# Sheet1.net
KiCad netlist of a schematic drawn in Altium Designer
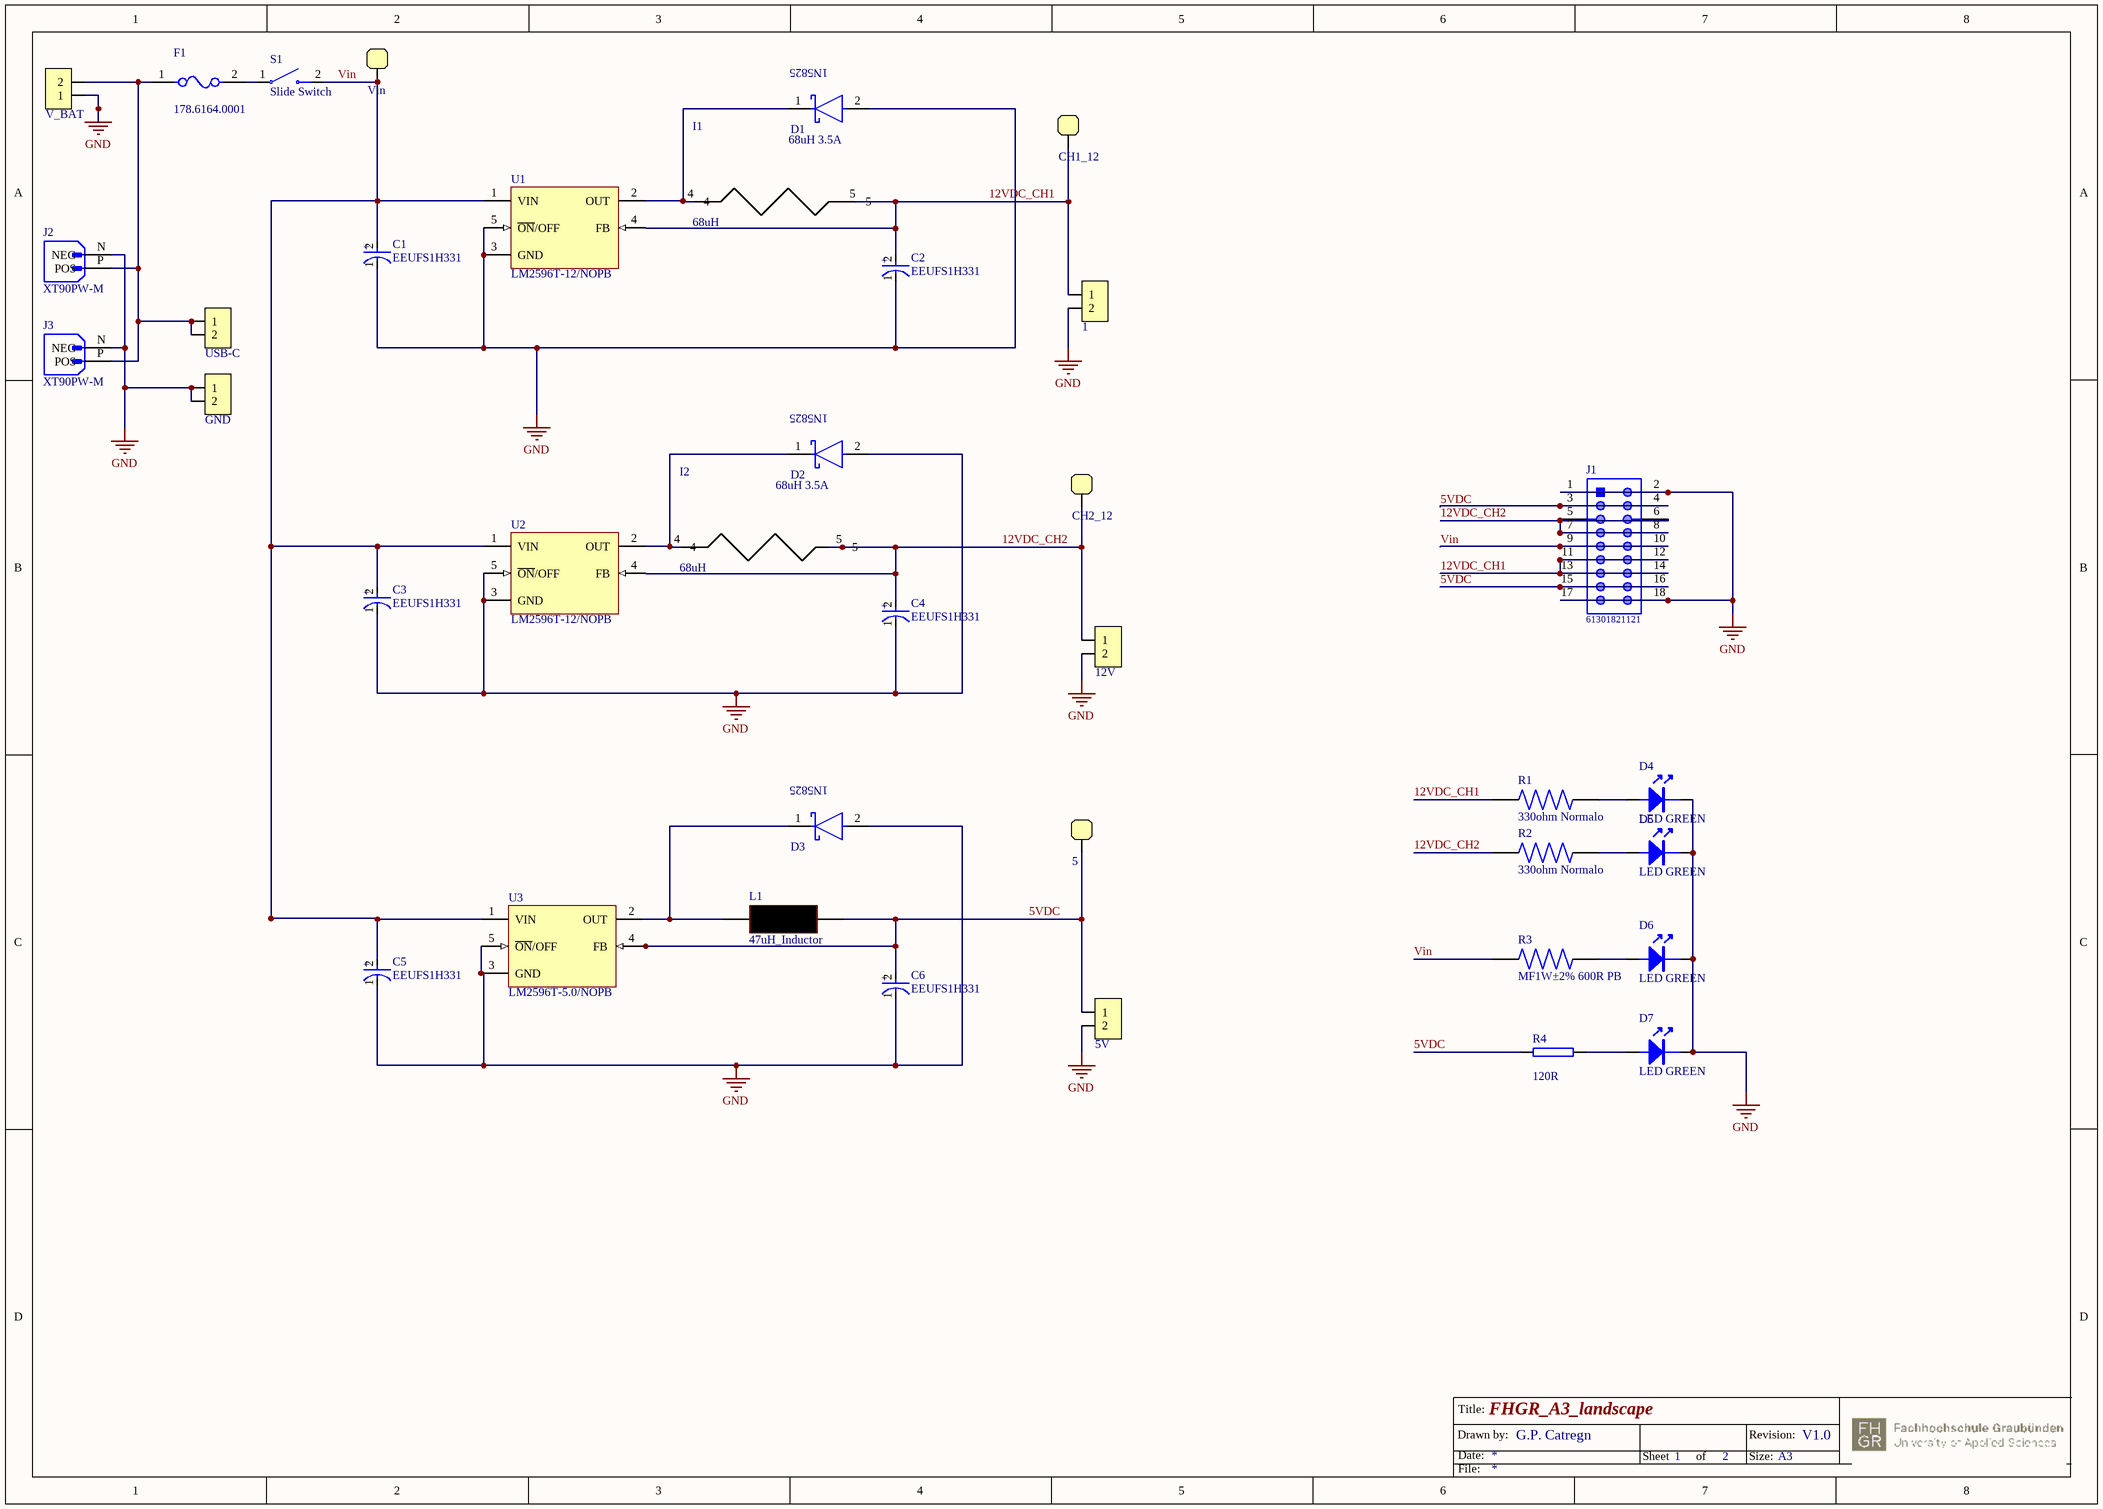
[diagram p0: Sheet1.SchDoc]

(export (version "E")
  (design (tool "Eeschema 10.0.6"))
  (components
    (comp (ref "1")
      (value "2Pin_Female")
      (footprint "OSTTE020104")
      (libsource (lib "FHGR_Altium_database") (part "Connector2Pin"))
    )
    (comp (ref "5") (value "MP") (footprint "MP_20") (libsource (lib "FHGR_Altium_database") (part "MP")))
    (comp (ref "5V")
      (value "2Pin_Female")
      (footprint "OSTTE020104")
      (libsource (lib "FHGR_Altium_database") (part "Connector2Pin"))
    )
    (comp (ref "12V")
      (value "2Pin_Female")
      (footprint "OSTTE020104")
      (libsource (lib "FHGR_Altium_database") (part "Connector2Pin"))
    )
    (comp (ref "C1")
      (value "EEUFS1H331")
      (footprint "FP-RAD-TH-D_10_0_5-L_20_2-MFG")
      (description "Aluminum Electrolytic Capacitors (Radial Lead Type) 330uF ±20% 50V")
      (libsource (lib "Altium Content Vault") (part "203bc49f2ac43e59fd269a8c329ed05"))
    )
    (comp (ref "C2")
      (value "EEUFS1H331")
      (footprint "FP-RAD-TH-D_10_0_5-L_20_2-MFG")
      (description "Aluminum Electrolytic Capacitors (Radial Lead Type) 330uF ±20% 50V")
      (libsource (lib "Altium Content Vault") (part "203bc49f2ac43e59fd269a8c329ed05"))
    )
    (comp (ref "C3")
      (value "EEUFS1H331")
      (footprint "FP-RAD-TH-D_10_0_5-L_20_2-MFG")
      (description "Aluminum Electrolytic Capacitors (Radial Lead Type) 330uF ±20% 50V")
      (libsource (lib "Altium Content Vault") (part "203bc49f2ac43e59fd269a8c329ed05"))
    )
    (comp (ref "C4")
      (value "EEUFS1H331")
      (footprint "FP-RAD-TH-D_10_0_5-L_20_2-MFG")
      (description "Aluminum Electrolytic Capacitors (Radial Lead Type) 330uF ±20% 50V")
      (libsource (lib "Altium Content Vault") (part "203bc49f2ac43e59fd269a8c329ed05"))
    )
    (comp (ref "C5")
      (value "EEUFS1H331")
      (footprint "FP-RAD-TH-D_10_0_5-L_20_2-MFG")
      (description "Aluminum Electrolytic Capacitors (Radial Lead Type) 330uF ±20% 50V")
      (libsource (lib "Altium Content Vault") (part "203bc49f2ac43e59fd269a8c329ed05"))
    )
    (comp (ref "C6")
      (value "EEUFS1H331")
      (footprint "FP-RAD-TH-D_10_0_5-L_20_2-MFG")
      (description "Aluminum Electrolytic Capacitors (Radial Lead Type) 330uF ±20% 50V")
      (libsource (lib "Altium Content Vault") (part "203bc49f2ac43e59fd269a8c329ed05"))
    )
    (comp (ref "CH1_12")
      (value "MP")
      (footprint "MP_20")
      (libsource (lib "FHGR_Altium_database") (part "MP"))
    )
    (comp (ref "CH2_12")
      (value "MP")
      (footprint "MP_20")
      (libsource (lib "FHGR_Altium_database") (part "MP"))
    )
    (comp (ref "D1")
      (value "1N5825")
      (footprint "Microsemi_1N5825_0")
      (libsource (lib "Diode_Microsemi_1N5825_eec") (part "1N5825"))
    )
    (comp (ref "D2")
      (value "1N5825")
      (footprint "Microsemi_1N5825_0")
      (libsource (lib "Diode_Microsemi_1N5825_eec") (part "1N5825"))
    )
    (comp (ref "D3")
      (value "1N5825")
      (footprint "Microsemi_1N5825_0")
      (libsource (lib "Diode_Microsemi_1N5825_eec") (part "1N5825"))
    )
    (comp (ref "D4")
      (value "LED GREEN")
      (footprint "LED_1206")
      (libsource (lib "FHGR_Altium_database") (part "LED"))
    )
    (comp (ref "D5")
      (value "LED GREEN")
      (footprint "LED_1206")
      (libsource (lib "FHGR_Altium_database") (part "LED"))
    )
    (comp (ref "D6")
      (value "LED GREEN")
      (footprint "LED_1206")
      (libsource (lib "FHGR_Altium_database") (part "LED"))
    )
    (comp (ref "D7")
      (value "LED GREEN")
      (footprint "LED_1206")
      (libsource (lib "FHGR_Altium_database") (part "LED"))
    )
    (comp (ref "F1")
      (value "178.6164.0001")
      (footprint "FP-178_6164_0001-MFG")
      (description "Fuse Holder  80V 1 Circuit Blade Through Hole")
      (fields (field (name "MANUFACTURER") "Littelfuse Inc"))
      (libsource (lib "Altium Content Vault") (part "5bcf9b9f640e542cf0359d10258e979"))
    )
    (comp (ref "GND")
      (value "2Pin_Male")
      (footprint "Header1x2_254")
      (libsource (lib "FHGR_Altium_database") (part "Connector2Pin"))
    )
    (comp (ref "I1")
      (value "68uH")
      (footprint "COIL 68uH LCLS1:PCBComponent_1")
      (libsource (lib "COIL 68uH LCLS") (part "Component_1"))
    )
    (comp (ref "I2")
      (value "68uH")
      (footprint "COIL 68uH LCLS1:PCBComponent_1")
      (libsource (lib "COIL 68uH LCLS") (part "Component_1"))
    )
    (comp (ref "J1")
      (value "61301821121")
      (footprint "61301821121")
      (description "THT Vertical Pin Header WR-PHD, Pitch 2.54 mm, Dual Row, 18 pins")
      (fields (field (name "MANUFACTURER") "Wurth Elektronik") (field (name "PUBLISHER") "WurthElektronik"))
      (libsource (lib "Altium Content Vault") (part "WE-CN-2P-M-R18"))
    )
    (comp (ref "J2")
      (value "XT90PW-M")
      (footprint "AMASS_XT90PW-M")
      (description "Socket; DC supply; XT90; male; PIN: 2; on PCBs; THT; Colour: yellow")
      (fields (field (name "MF") "AMASS"))
      (libsource (lib "XT90PW-M") (part "XT90PW-M"))
    )
    (comp (ref "J3")
      (value "XT90PW-M")
      (footprint "AMASS_XT90PW-M")
      (description "Socket; DC supply; XT90; male; PIN: 2; on PCBs; THT; Colour: yellow")
      (fields (field (name "MF") "AMASS"))
      (libsource (lib "XT90PW-M") (part "XT90PW-M"))
    )
    (comp (ref "L1")
      (value "47uH_Inductor")
      (footprint "INDM120120X100N")
      (description "Inductor 47uH")
      (libsource (lib "YPRH1209_Inductor_47uH") (part "YPRH1209_47uH_Inductor"))
    )
    (comp (ref "R1")
      (value "330ohm Normalo")
      (footprint "RESAD1100W55L680D260")
      (description "1.07 kOhms Â±1% 0.25W, 1/4W Through Hole Resistor Axial - Metal Film")
      (fields (field (name "MF") "Yageo") (field (name "MP") "MFR-25FBF52-1K"))
      (libsource (lib "MFR-25FBF52-1K") (part "MFR-25FBF52-1K"))
    )
    (comp (ref "R2")
      (value "330ohm Normalo")
      (footprint "RESAD1100W55L680D260")
      (description "1.07 kOhms Â±1% 0.25W, 1/4W Through Hole Resistor Axial - Metal Film")
      (fields (field (name "MF") "Yageo") (field (name "MP") "MFR-25FBF52-1K"))
      (libsource (lib "MFR-25FBF52-1K") (part "MFR-25FBF52-1K"))
    )
    (comp (ref "R3")
      (value "MF1W±2% 600R PB")
      (footprint "RESAD1100W55L680D260")
      (description "1.07 kOhms Â±1% 0.25W, 1/4W Through Hole Resistor Axial - Metal Film")
      (fields (field (name "MF") "Yageo") (field (name "MP") "MFR-25FBF52-1K"))
      (libsource (lib "MFR-25FBF52-1K") (part "MFR-25FBF52-1K"))
    )
    (comp (ref "R4")
      (value "120R")
      (footprint "0805")
      (fields (field (name "TOLERANCE") "1%") (field (name "Comment") "R 120R 0805"))
      (libsource (lib "FHGR_Altium_database") (part "Resistor"))
    )
    (comp (ref "S1")
      (value "Slide Switch")
      (footprint "SW_GF_123_0054")
      (fields (field (name "VOLTAGE") "125V"))
      (libsource (lib "FHGR_Altium_database") (part "Switch_Slide"))
    )
    (comp (ref "U1")
      (value "LM2596T-12/NOPB")
      (footprint "NDH0005A")
      (description "SIMPLE SWITCHER® Power Converter 150 KHz 3A Step-Down Voltage Regulator, 5-pin TO-220, Pb-Free")
      (fields (field (name "MANUFACTURER") "Texas Instruments"))
      (libsource (lib "Altium Content Vault") (part "PM-REG-LM2575HVT-12"))
    )
    (comp (ref "U2")
      (value "LM2596T-12/NOPB")
      (footprint "NDH0005A")
      (description "SIMPLE SWITCHER® Power Converter 150 KHz 3A Step-Down Voltage Regulator, 5-pin TO-220, Pb-Free")
      (fields (field (name "MANUFACTURER") "Texas Instruments"))
      (libsource (lib "Altium Content Vault") (part "PM-REG-LM2575HVT-12"))
    )
    (comp (ref "U3")
      (value "LM2596T-5.0/NOPB")
      (footprint "NDH0005A")
      (description "SIMPLE SWITCHER® Power Converter 150 KHz 3A Step-Down Voltage Regulator, 5-pin TO-220, Pb-Free")
      (fields (field (name "MANUFACTURER") "Texas Instruments"))
      (libsource (lib "Altium Content Vault") (part "PM-REG-LM2575HVT-12"))
    )
    (comp (ref "USB-C")
      (value "2Pin_Male")
      (footprint "Header1x2_254")
      (libsource (lib "FHGR_Altium_database") (part "Connector2Pin"))
    )
    (comp (ref "Vin") (value "MP") (footprint "MP_20") (libsource (lib "FHGR_Altium_database") (part "MP")))
    (comp (ref "V_BAT")
      (value "2Pin_Female")
      (footprint "OSTTE020104")
      (libsource (lib "") (part "Connector2Pin_1"))
    )
  )
  (nets
    (net (code "1") (name "/5VDC") (class "Default")
      (node (ref "5") (pin "1") (pinfunction "1_1") (pintype "passive"))
      (node (ref "5V") (pin "1") (pinfunction "1_1") (pintype "passive"))
      (node (ref "C6") (pin "2") (pinfunction "A_2") (pintype "passive"))
      (node (ref "J1") (pin "15") (pinfunction "15_15") (pintype "passive"))
      (node (ref "J1") (pin "16") (pinfunction "16_16") (pintype "passive"))
      (node (ref "J1") (pin "3") (pinfunction "3_3") (pintype "passive"))
      (node (ref "J1") (pin "4") (pinfunction "4_4") (pintype "passive"))
      (node (ref "L1") (pin "2") (pintype "passive"))
      (node (ref "R4") (pin "1") (pintype "passive"))
      (node (ref "U3") (pin "4") (pinfunction "FB_4") (pintype "input"))
    )
    (net (code "2") (name "/12VDC_CH1") (class "Default")
      (node (ref "1") (pin "1") (pinfunction "1_1") (pintype "passive"))
      (node (ref "C2") (pin "2") (pinfunction "A_2") (pintype "passive"))
      (node (ref "CH1_12") (pin "1") (pinfunction "1_1") (pintype "passive"))
      (node (ref "I1") (pin "5") (pinfunction "5_5") (pintype "passive"))
      (node (ref "J1") (pin "11") (pinfunction "11_11") (pintype "passive"))
      (node (ref "J1") (pin "12") (pinfunction "12_12") (pintype "passive"))
      (node (ref "J1") (pin "13") (pinfunction "13_13") (pintype "passive"))
      (node (ref "J1") (pin "14") (pinfunction "14_14") (pintype "passive"))
      (node (ref "R1") (pin "1") (pinfunction "1_1") (pintype "passive"))
      (node (ref "U1") (pin "4") (pinfunction "FB_4") (pintype "input"))
    )
    (net (code "3") (name "/12VDC_CH2") (class "Default")
      (node (ref "12V") (pin "1") (pinfunction "1_1") (pintype "passive"))
      (node (ref "C4") (pin "2") (pinfunction "A_2") (pintype "passive"))
      (node (ref "CH2_12") (pin "1") (pinfunction "1_1") (pintype "passive"))
      (node (ref "I2") (pin "5") (pinfunction "5_5") (pintype "passive"))
      (node (ref "J1") (pin "5") (pinfunction "5_5") (pintype "passive"))
      (node (ref "J1") (pin "6") (pinfunction "6_6") (pintype "passive"))
      (node (ref "J1") (pin "7") (pinfunction "7_7") (pintype "passive"))
      (node (ref "J1") (pin "8") (pinfunction "8_8") (pintype "passive"))
      (node (ref "R2") (pin "1") (pinfunction "1_1") (pintype "passive"))
      (node (ref "U2") (pin "4") (pinfunction "FB_4") (pintype "input"))
    )
    (net (code "4") (name "/Vin") (class "Default")
      (node (ref "C1") (pin "2") (pinfunction "A_2") (pintype "passive"))
      (node (ref "C3") (pin "2") (pinfunction "A_2") (pintype "passive"))
      (node (ref "C5") (pin "2") (pinfunction "A_2") (pintype "passive"))
      (node (ref "J1") (pin "10") (pinfunction "10_10") (pintype "passive"))
      (node (ref "J1") (pin "9") (pinfunction "9_9") (pintype "passive"))
      (node (ref "R3") (pin "1") (pinfunction "1_1") (pintype "passive"))
      (node (ref "S1") (pin "2") (pinfunction "C_2") (pintype "passive"))
      (node (ref "U1") (pin "1") (pinfunction "VIN_1") (pintype "power_in"))
      (node (ref "U2") (pin "1") (pinfunction "VIN_1") (pintype "power_in"))
      (node (ref "U3") (pin "1") (pinfunction "VIN_1") (pintype "power_in"))
      (node (ref "Vin") (pin "1") (pinfunction "1_1") (pintype "passive"))
    )
    (net (code "5") (name "GND") (class "Default")
      (node (ref "1") (pin "2") (pinfunction "2_2") (pintype "passive"))
      (node (ref "12V") (pin "2") (pinfunction "2_2") (pintype "passive"))
      (node (ref "5V") (pin "2") (pinfunction "2_2") (pintype "passive"))
      (node (ref "C1") (pin "1") (pinfunction "C_1") (pintype "passive"))
      (node (ref "C2") (pin "1") (pinfunction "C_1") (pintype "passive"))
      (node (ref "C3") (pin "1") (pinfunction "C_1") (pintype "passive"))
      (node (ref "C4") (pin "1") (pinfunction "C_1") (pintype "passive"))
      (node (ref "C5") (pin "1") (pinfunction "C_1") (pintype "passive"))
      (node (ref "C6") (pin "1") (pinfunction "C_1") (pintype "passive"))
      (node (ref "D1") (pin "2") (pinfunction "A_2") (pintype "passive"))
      (node (ref "D2") (pin "2") (pinfunction "A_2") (pintype "passive"))
      (node (ref "D3") (pin "2") (pinfunction "A_2") (pintype "passive"))
      (node (ref "D4") (pin "K") (pintype "passive"))
      (node (ref "D5") (pin "K") (pintype "passive"))
      (node (ref "D6") (pin "K") (pintype "passive"))
      (node (ref "D7") (pin "K") (pintype "passive"))
      (node (ref "GND") (pin "1") (pinfunction "1_1") (pintype "passive"))
      (node (ref "GND") (pin "2") (pinfunction "2_2") (pintype "passive"))
      (node (ref "J1") (pin "1") (pinfunction "1_1") (pintype "passive"))
      (node (ref "J1") (pin "17") (pinfunction "17_17") (pintype "passive"))
      (node (ref "J1") (pin "18") (pinfunction "18_18") (pintype "passive"))
      (node (ref "J1") (pin "2") (pinfunction "2_2") (pintype "passive"))
      (node (ref "J2") (pin "N") (pinfunction "NEG_N") (pintype "passive"))
      (node (ref "J3") (pin "N") (pinfunction "NEG_N") (pintype "passive"))
      (node (ref "U1") (pin "3") (pinfunction "GND_3") (pintype "power_in"))
      (node (ref "U1") (pin "5") (pinfunction "~{ON}/OFF_5") (pintype "input"))
      (node (ref "U2") (pin "3") (pinfunction "GND_3") (pintype "power_in"))
      (node (ref "U2") (pin "5") (pinfunction "~{ON}/OFF_5") (pintype "input"))
      (node (ref "U3") (pin "3") (pinfunction "GND_3") (pintype "power_in"))
      (node (ref "U3") (pin "5") (pinfunction "~{ON}/OFF_5") (pintype "input"))
      (node (ref "V_BAT") (pin "1") (pinfunction "1_1") (pintype "passive"))
    )
    (net (code "6") (name "Net-(D1-C)") (class "Default")
      (node (ref "D1") (pin "1") (pinfunction "C_1") (pintype "passive"))
      (node (ref "I1") (pin "4") (pinfunction "4_4") (pintype "passive"))
      (node (ref "U1") (pin "2") (pinfunction "OUT_2") (pintype "power_in"))
    )
    (net (code "7") (name "Net-(D2-C)") (class "Default")
      (node (ref "D2") (pin "1") (pinfunction "C_1") (pintype "passive"))
      (node (ref "I2") (pin "4") (pinfunction "4_4") (pintype "passive"))
      (node (ref "U2") (pin "2") (pinfunction "OUT_2") (pintype "power_in"))
    )
    (net (code "8") (name "Net-(D3-C)") (class "Default")
      (node (ref "D3") (pin "1") (pinfunction "C_1") (pintype "passive"))
      (node (ref "L1") (pin "1") (pintype "passive"))
      (node (ref "U3") (pin "2") (pinfunction "OUT_2") (pintype "power_in"))
    )
    (net (code "9") (name "Net-(D4-PadA)") (class "Default")
      (node (ref "D4") (pin "A") (pintype "passive"))
      (node (ref "R1") (pin "2") (pinfunction "2_2") (pintype "passive"))
    )
    (net (code "10") (name "Net-(D5-PadA)") (class "Default")
      (node (ref "D5") (pin "A") (pintype "passive"))
      (node (ref "R2") (pin "2") (pinfunction "2_2") (pintype "passive"))
    )
    (net (code "11") (name "Net-(D6-PadA)") (class "Default")
      (node (ref "D6") (pin "A") (pintype "passive"))
      (node (ref "R3") (pin "2") (pinfunction "2_2") (pintype "passive"))
    )
    (net (code "12") (name "Net-(D7-PadA)") (class "Default")
      (node (ref "D7") (pin "A") (pintype "passive"))
      (node (ref "R4") (pin "2") (pintype "passive"))
    )
    (net (code "13") (name "Net-(J2-POS)") (class "Default")
      (node (ref "F1") (pin "1") (pinfunction "1_1") (pintype "passive"))
      (node (ref "J2") (pin "P") (pinfunction "POS_P") (pintype "passive"))
      (node (ref "J3") (pin "P") (pinfunction "POS_P") (pintype "passive"))
      (node (ref "USB-C") (pin "1") (pinfunction "1_1") (pintype "passive"))
      (node (ref "USB-C") (pin "2") (pinfunction "2_2") (pintype "passive"))
      (node (ref "V_BAT") (pin "2") (pinfunction "2_2") (pintype "passive"))
    )
    (net (code "14") (name "Net-(S1-A)") (class "Default")
      (node (ref "F1") (pin "2") (pinfunction "2_2") (pintype "passive"))
      (node (ref "S1") (pin "1") (pinfunction "A_1") (pintype "passive"))
    )
  )
)
